# USB.net
KiCad netlist of a schematic drawn in Altium Designer
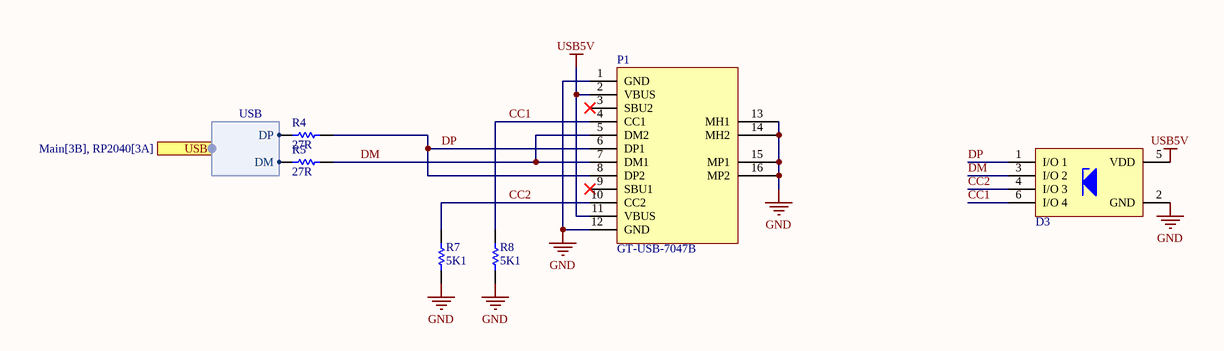
[diagram p0: USB.SchDoc]

(export (version "E")
  (design (tool "Eeschema 10.0.6"))
  (components
    (comp (ref "D3")
      (value "3.3V")
      (footprint "WE-TVS_SOT23-6L")
      (description "Shenzhen JingYang TT0514VL")
      (fields
        (field (name "MANUFACTURER PART NUMBER") "824015043")
        (field (name "MANUFACTURER") "Wurth Elektronik")
      )
      (libsource (lib "Altium_WE-TVS (rev22b)") (part "824015043"))
    )
    (comp (ref "P1")
      (value "GT-USB-7047B")
      (footprint "GT-USB-7047B")
      (libsource (lib "Custom Components") (part "GT-USB-7047B"))
    )
    (comp (ref "R4")
      (value "27R")
      (footprint "RESC0603(1608)_N")
      (description "Chipwiderstand, Oberflächenmontage, Dickschicht, 27 ohm, 50 V, 0603 [Metrisch 1608], 100 mW, ± 1%")
      (fields (field (name "MANUFACTURER") "Multicomp"))
      (libsource (lib "Standardbauteile") (part "Res 27R"))
    )
    (comp (ref "R5")
      (value "27R")
      (footprint "RESC0603(1608)_N")
      (description "Chipwiderstand, Oberflächenmontage, Dickschicht, 27 ohm, 50 V, 0603 [Metrisch 1608], 100 mW, ± 1%")
      (fields (field (name "MANUFACTURER") "Multicomp"))
      (libsource (lib "Standardbauteile") (part "Res 27R"))
    )
    (comp (ref "R7")
      (value "5K1")
      (footprint "RESC0603(1608)_N")
      (description "Chipwiderstand, SMD, Baureihe MC, 5%")
      (fields (field (name "MANUFACTURER") "Multicomp"))
      (libsource (lib "Standardbauteile") (part "Res 5K6"))
    )
    (comp (ref "R8")
      (value "5K1")
      (footprint "RESC0603(1608)_N")
      (description "Chipwiderstand, SMD, Baureihe MC, 5%")
      (fields (field (name "MANUFACTURER") "Multicomp"))
      (libsource (lib "Standardbauteile") (part "Res 5K6"))
    )
  )
  (nets
    (net (code "2") (name "/CC1") (class "Default")
      (node (ref "D3") (pin "6") (pinfunction "I/O_4_6") (pintype "passive"))
      (node (ref "P1") (pin "4") (pinfunction "CC1_4") (pintype "passive"))
      (node (ref "R8") (pin "2") (pinfunction "2_2") (pintype "passive"))
    )
    (net (code "3") (name "/CC2") (class "Default")
      (node (ref "D3") (pin "4") (pinfunction "I/O_3_4") (pintype "passive"))
      (node (ref "P1") (pin "10") (pinfunction "CC2_10") (pintype "passive"))
      (node (ref "R7") (pin "2") (pinfunction "2_2") (pintype "passive"))
    )
    (net (code "4") (name "/DM") (class "Default")
      (node (ref "D3") (pin "3") (pinfunction "I/O_2_3") (pintype "passive"))
      (node (ref "P1") (pin "5") (pinfunction "DM2_5") (pintype "passive"))
      (node (ref "P1") (pin "7") (pinfunction "DM1_7") (pintype "passive"))
      (node (ref "R5") (pin "2") (pinfunction "2_2") (pintype "passive"))
    )
    (net (code "5") (name "/DP") (class "Default")
      (node (ref "D3") (pin "1") (pinfunction "I/O_1_1") (pintype "passive"))
      (node (ref "P1") (pin "6") (pinfunction "DP1_6") (pintype "passive"))
      (node (ref "P1") (pin "8") (pinfunction "DP2_8") (pintype "passive"))
      (node (ref "R4") (pin "2") (pinfunction "2_2") (pintype "passive"))
    )
    (net (code "7") (name "GND") (class "Default")
      (node (ref "D3") (pin "2") (pinfunction "GND_2") (pintype "passive"))
      (node (ref "P1") (pin "1") (pinfunction "GND_1") (pintype "passive"))
      (node (ref "P1") (pin "12") (pinfunction "GND_12") (pintype "passive"))
      (node (ref "P1") (pin "13") (pinfunction "MH1_13") (pintype "passive"))
      (node (ref "P1") (pin "14") (pinfunction "MH2_14") (pintype "passive"))
      (node (ref "P1") (pin "15") (pinfunction "MP1_15") (pintype "passive"))
      (node (ref "P1") (pin "16") (pinfunction "MP2_16") (pintype "passive"))
      (node (ref "R7") (pin "1") (pinfunction "1_1") (pintype "passive"))
      (node (ref "R8") (pin "1") (pinfunction "1_1") (pintype "passive"))
    )
    (net (code "8") (name "USB5V") (class "Default")
      (node (ref "D3") (pin "5") (pinfunction "VDD_5") (pintype "passive"))
      (node (ref "P1") (pin "11") (pinfunction "VBUS_11") (pintype "passive"))
      (node (ref "P1") (pin "2") (pinfunction "VBUS_2") (pintype "passive"))
    )
    (net (code "9") (name "unconnected-(P1-SBU1-Pad9)") (class "Default")
      (node (ref "P1") (pin "9") (pinfunction "SBU1_9") (pintype "passive+no_connect"))
    )
    (net (code "10") (name "unconnected-(P1-SBU2-Pad3)") (class "Default")
      (node (ref "P1") (pin "3") (pinfunction "SBU2_3") (pintype "passive+no_connect"))
    )
    (net (code "11") (name "unconnected-(R4-Pad1)") (class "Default")
      (node (ref "R4") (pin "1") (pinfunction "1_1") (pintype "passive"))
    )
    (net (code "12") (name "unconnected-(R5-Pad1)") (class "Default")
      (node (ref "R5") (pin "1") (pinfunction "1_1") (pintype "passive"))
    )
  )
)
